# Bluepill_and_Power.net
KiCad netlist of a schematic drawn in Altium Designer
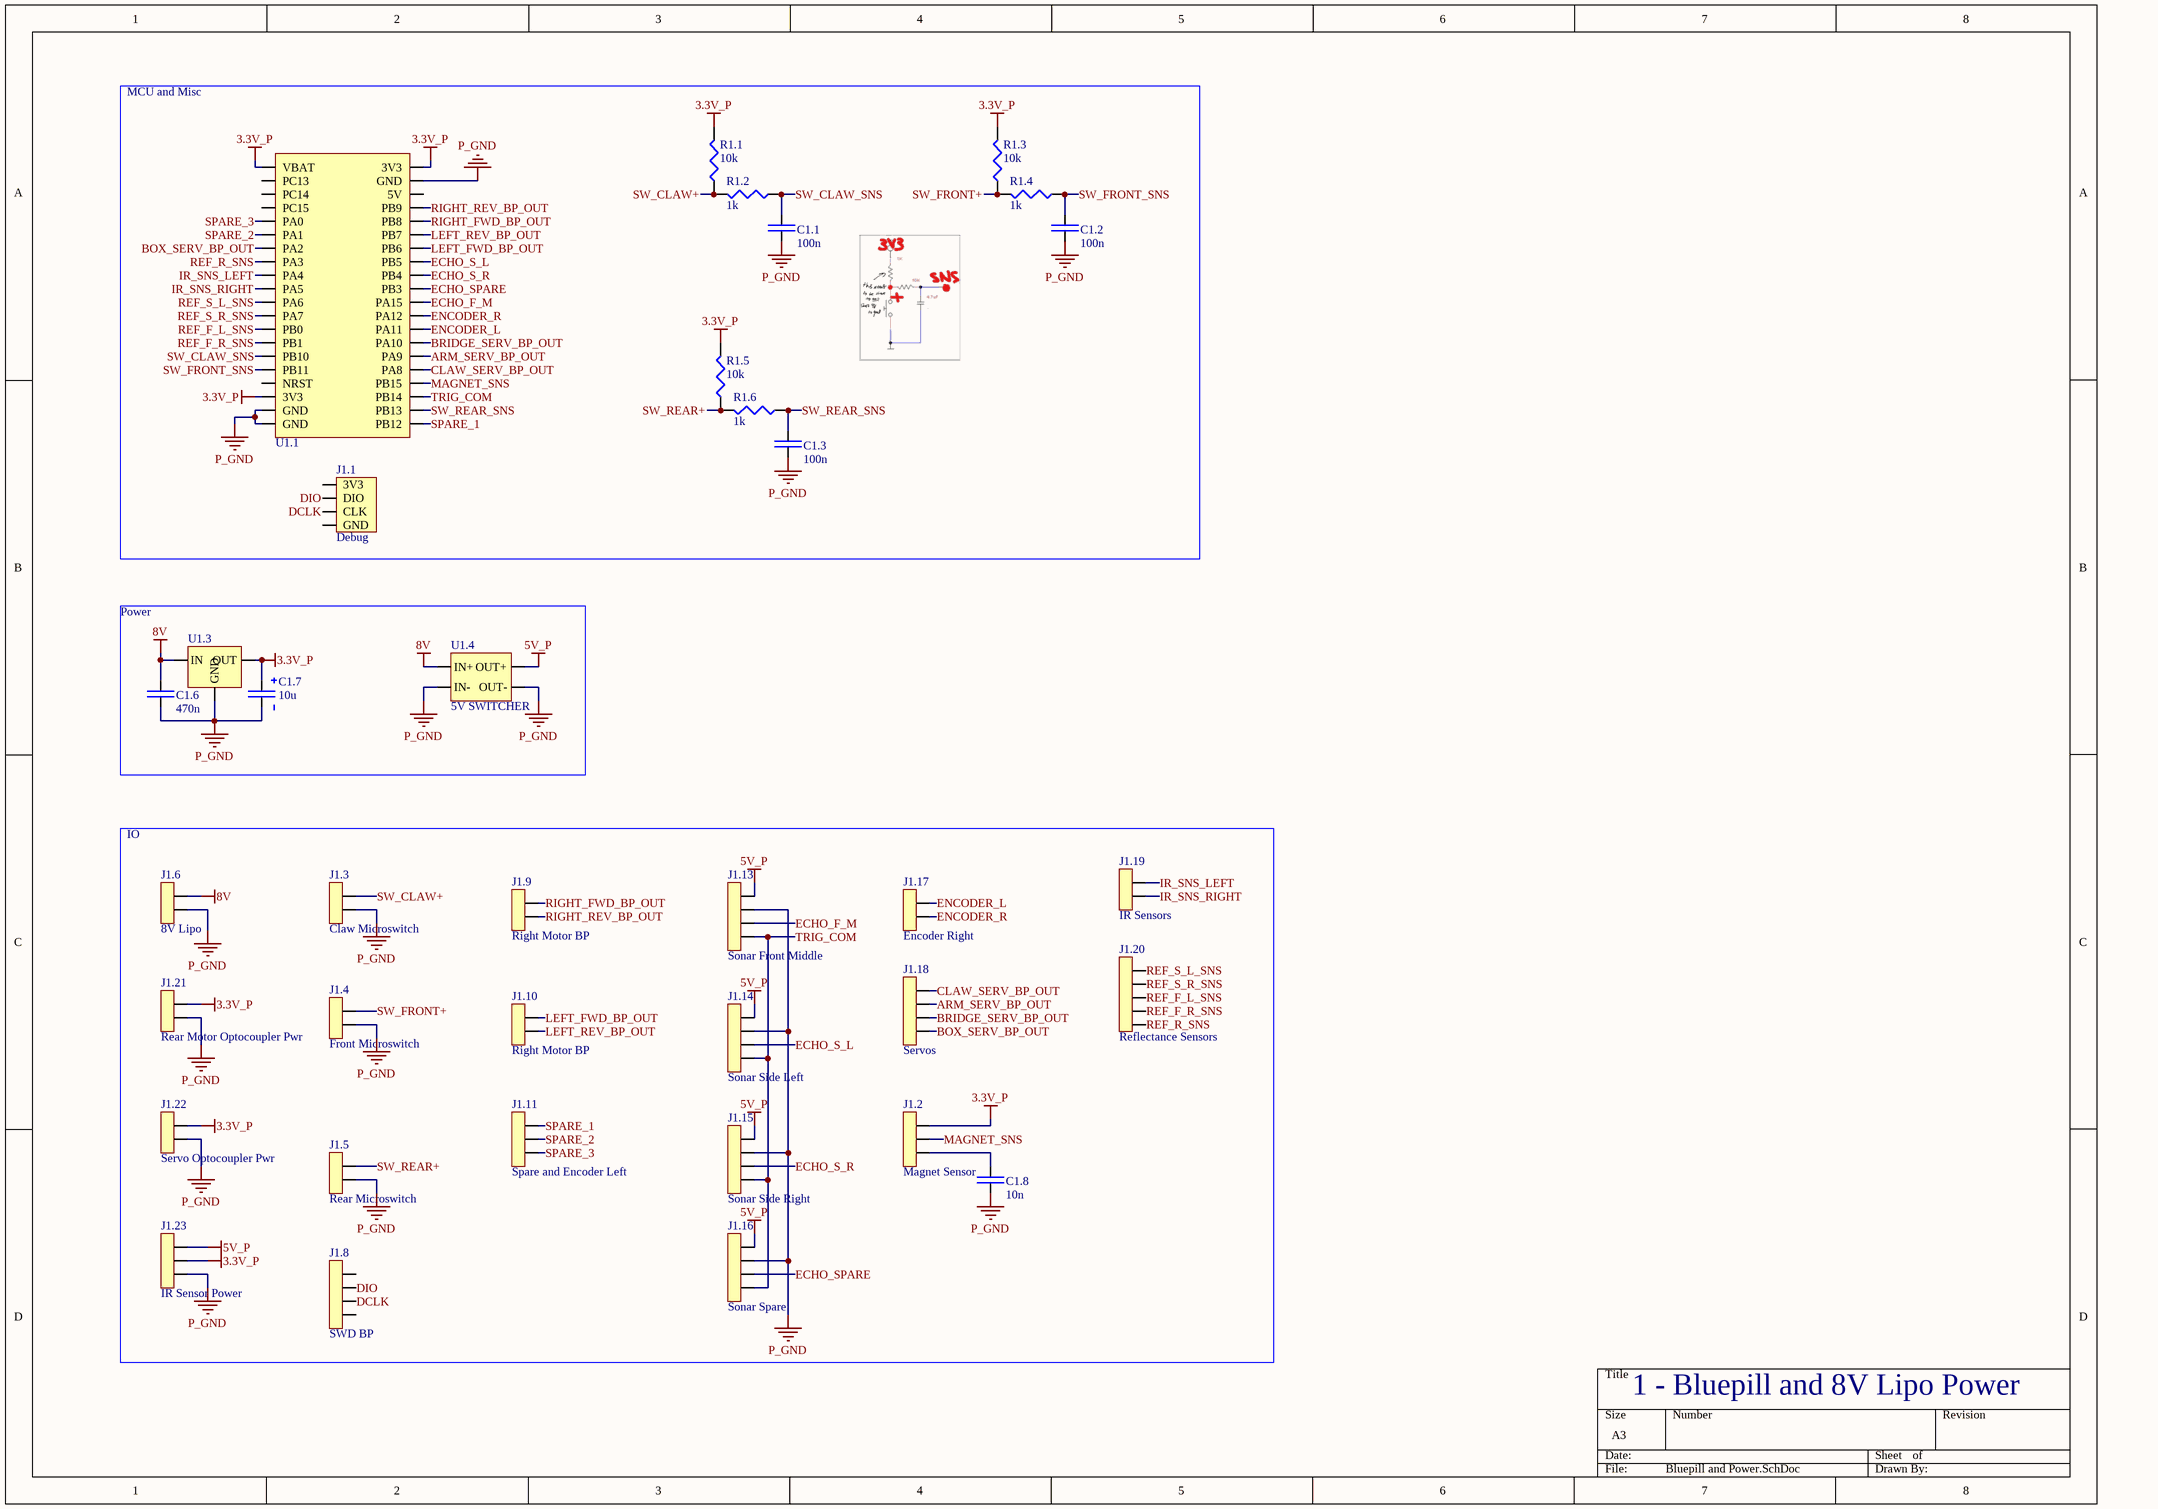
[diagram p0: Bluepill and Power.SchDoc]

(export (version "E")
  (design (tool "Eeschema 10.0.6"))
  (components
    (comp (ref "C1.1")
      (value "100n")
      (footprint "Non Polarized Cap")
      (libsource (lib "SPICEBot_SchLib") (part "Cap_Generic"))
    )
    (comp (ref "C1.2")
      (value "100n")
      (footprint "Non Polarized Cap")
      (libsource (lib "SPICEBot_SchLib") (part "Cap_Generic"))
    )
    (comp (ref "C1.3")
      (value "100n")
      (footprint "Non Polarized Cap")
      (libsource (lib "SPICEBot_SchLib") (part "Cap_Generic"))
    )
    (comp (ref "C1.6")
      (value "470n")
      (footprint "Non Polarized Cap")
      (libsource (lib "SPICEBot_SchLib") (part "Cap_Generic"))
    )
    (comp (ref "C1.7")
      (value "10u")
      (footprint "Polarized Cap")
      (libsource (lib "SPICEBot_SchLib") (part "Polarized Cap"))
    )
    (comp (ref "C1.8")
      (value "10n")
      (footprint "Non Polarized Cap")
      (libsource (lib "SPICEBot_SchLib") (part "Cap_Generic"))
    )
    (comp (ref "J1.1")
      (value "Debug")
      (footprint "Four Pads")
      (libsource (lib "SPICEBot_SchLib") (part "BP SWD Conn"))
    )
    (comp (ref "J1.2")
      (value "Magnet Sensor")
      (footprint "3pos JST")
      (description "3pos Conn")
      (libsource (lib "SPICEBot_SchLib") (part "3pos Conn"))
    )
    (comp (ref "J1.3")
      (value "Claw Microswitch")
      (footprint "2pos JST")
      (description "2pos Conn JST")
      (libsource (lib "SPICEBot_SchLib") (part "2pos Conn"))
    )
    (comp (ref "J1.4")
      (value "Front Microswitch")
      (footprint "2pos JST")
      (description "2pos Conn JST")
      (libsource (lib "SPICEBot_SchLib") (part "2pos Conn"))
    )
    (comp (ref "J1.5")
      (value "Rear Microswitch")
      (footprint "2pos JST")
      (description "2pos Conn JST")
      (libsource (lib "SPICEBot_SchLib") (part "2pos Conn"))
    )
    (comp (ref "J1.6")
      (value "8V Lipo")
      (footprint "2pos JST")
      (description "2pos Conn JST")
      (libsource (lib "SPICEBot_SchLib") (part "2pos Conn"))
    )
    (comp (ref "J1.8")
      (value "SWD BP")
      (footprint "4Pos JST")
      (description "4pos Conn")
      (libsource (lib "SPICEBot_SchLib") (part "4pos Conn"))
    )
    (comp (ref "J1.9")
      (value "Right Motor BP")
      (footprint "2pos JST")
      (description "2pos Conn JST")
      (libsource (lib "SPICEBot_SchLib") (part "2pos Conn"))
    )
    (comp (ref "J1.10")
      (value "Right Motor BP")
      (footprint "2pos JST")
      (description "2pos Conn JST")
      (libsource (lib "SPICEBot_SchLib") (part "2pos Conn"))
    )
    (comp (ref "J1.11")
      (value "Spare and Encoder Left")
      (footprint "3pos JST")
      (description "3pos Conn")
      (libsource (lib "SPICEBot_SchLib") (part "3pos Conn"))
    )
    (comp (ref "J1.13")
      (value "Sonar Front Middle")
      (footprint "4Pos JST")
      (description "4pos Conn")
      (libsource (lib "SPICEBot_SchLib") (part "4pos Conn"))
    )
    (comp (ref "J1.14")
      (value "Sonar Side Left")
      (footprint "4Pos JST")
      (description "4pos Conn")
      (libsource (lib "SPICEBot_SchLib") (part "4pos Conn"))
    )
    (comp (ref "J1.15")
      (value "Sonar Side Right")
      (footprint "4Pos JST")
      (description "4pos Conn")
      (libsource (lib "SPICEBot_SchLib") (part "4pos Conn"))
    )
    (comp (ref "J1.16")
      (value "Sonar Spare")
      (footprint "4Pos JST")
      (description "4pos Conn")
      (libsource (lib "SPICEBot_SchLib") (part "4pos Conn"))
    )
    (comp (ref "J1.17")
      (value "Encoder Right")
      (footprint "2pos JST")
      (description "2pos Conn JST")
      (libsource (lib "SPICEBot_SchLib") (part "2pos Conn"))
    )
    (comp (ref "J1.18")
      (value "Servos")
      (footprint "4Pos JST")
      (description "4pos Conn")
      (libsource (lib "SPICEBot_SchLib") (part "4pos Conn"))
    )
    (comp (ref "J1.19")
      (value "IR Sensors")
      (footprint "2pos JST")
      (description "2pos Conn JST")
      (libsource (lib "SPICEBot_SchLib") (part "2pos Conn"))
    )
    (comp (ref "J1.20")
      (value "Reflectance Sensors")
      (footprint "5POS JST")
      (description "5pos Conn JST")
      (libsource (lib "SPICEBot_SchLib") (part "5pos Conn"))
    )
    (comp (ref "J1.21")
      (value "Rear Motor Optocoupler Pwr")
      (footprint "2pos JST")
      (description "2pos Conn JST")
      (libsource (lib "SPICEBot_SchLib") (part "2pos Conn"))
    )
    (comp (ref "J1.22")
      (value "Servo Optocoupler Pwr")
      (footprint "2pos JST")
      (description "2pos Conn JST")
      (libsource (lib "SPICEBot_SchLib") (part "2pos Conn"))
    )
    (comp (ref "J1.23")
      (value "IR Sensor Power")
      (footprint "3pos JST")
      (description "3pos Conn")
      (libsource (lib "SPICEBot_SchLib") (part "3pos Conn"))
    )
    (comp (ref "R1.1")
      (value "10k")
      (footprint "Res_Generic")
      (libsource (lib "SPICEBot_SchLib") (part "Res_Generic"))
    )
    (comp (ref "R1.2")
      (value "1k")
      (footprint "Res_Generic")
      (libsource (lib "SPICEBot_SchLib") (part "Res_Generic"))
    )
    (comp (ref "R1.3")
      (value "10k")
      (footprint "Res_Generic")
      (libsource (lib "SPICEBot_SchLib") (part "Res_Generic"))
    )
    (comp (ref "R1.4")
      (value "1k")
      (footprint "Res_Generic")
      (libsource (lib "SPICEBot_SchLib") (part "Res_Generic"))
    )
    (comp (ref "R1.5")
      (value "10k")
      (footprint "Res_Generic")
      (libsource (lib "SPICEBot_SchLib") (part "Res_Generic"))
    )
    (comp (ref "R1.6")
      (value "1k")
      (footprint "Res_Generic")
      (libsource (lib "SPICEBot_SchLib") (part "Res_Generic"))
    )
    (comp (ref "U1.1")
      (value "Bluepill")
      (footprint "DIP40")
      (description "STM32F103C8T6")
      (libsource (lib "SPICEBot_SchLib") (part "Bluepill"))
    )
    (comp (ref "U1.3")
      (value "3.3V")
      (footprint "TO220")
      (description "MC33269 IC REG LINEAR 3.3V 800MA TO220-3")
      (libsource (lib "SPICEBot_SchLib") (part "MC33269 3.3V Reg"))
    )
    (comp (ref "U1.4")
      (value "5V SWITCHER")
      (footprint "ADJ Switcher")
      (description "Adjutable Switcher 3.5A Max")
      (libsource (lib "SPICEBot_SchLib") (part "LM2596S"))
    )
  )
  (nets
    (net (code "1") (name "/ARM_SERV_BP_OUT") (class "Default")
      (node (ref "J1.18") (pin "3") (pinfunction "3_3") (pintype "passive"))
      (node (ref "U1.1") (pin "26") (pinfunction "PA9_26") (pintype "passive"))
    )
    (net (code "2") (name "/BOX_SERV_BP_OUT") (class "Default")
      (node (ref "J1.18") (pin "1") (pinfunction "1_1") (pintype "passive"))
      (node (ref "U1.1") (pin "7") (pinfunction "PA2_7") (pintype "passive"))
    )
    (net (code "3") (name "/BRIDGE_SERV_BP_OUT") (class "Default")
      (node (ref "J1.18") (pin "2") (pinfunction "2_2") (pintype "passive"))
      (node (ref "U1.1") (pin "27") (pinfunction "PA10_27") (pintype "passive"))
    )
    (net (code "4") (name "/CLAW_SERV_BP_OUT") (class "Default")
      (node (ref "J1.18") (pin "4") (pinfunction "4_4") (pintype "passive"))
      (node (ref "U1.1") (pin "25") (pinfunction "PA8_25") (pintype "passive"))
    )
    (net (code "5") (name "/DCLK") (class "Default")
      (node (ref "J1.1") (pin "3") (pinfunction "CLK_3") (pintype "passive"))
      (node (ref "J1.8") (pin "2") (pinfunction "2_2") (pintype "passive"))
    )
    (net (code "6") (name "/DIO") (class "Default")
      (node (ref "J1.1") (pin "2") (pinfunction "DIO_2") (pintype "passive"))
      (node (ref "J1.8") (pin "3") (pinfunction "3_3") (pintype "passive"))
    )
    (net (code "7") (name "/ECHO_F_M") (class "Default")
      (node (ref "J1.13") (pin "2") (pinfunction "2_2") (pintype "passive"))
      (node (ref "U1.1") (pin "30") (pinfunction "PA15_30") (pintype "passive"))
    )
    (net (code "8") (name "/ECHO_SPARE") (class "Default")
      (node (ref "J1.16") (pin "2") (pinfunction "2_2") (pintype "passive"))
      (node (ref "U1.1") (pin "31") (pinfunction "PB3_31") (pintype "passive"))
    )
    (net (code "9") (name "/ECHO_S_L") (class "Default")
      (node (ref "J1.14") (pin "2") (pinfunction "2_2") (pintype "passive"))
      (node (ref "U1.1") (pin "33") (pinfunction "PB5_33") (pintype "passive"))
    )
    (net (code "10") (name "/ECHO_S_R") (class "Default")
      (node (ref "J1.15") (pin "2") (pinfunction "2_2") (pintype "passive"))
      (node (ref "U1.1") (pin "32") (pinfunction "PB4_32") (pintype "passive"))
    )
    (net (code "11") (name "/ENCODER_L") (class "Default")
      (node (ref "J1.17") (pin "2") (pinfunction "2_2") (pintype "passive"))
      (node (ref "U1.1") (pin "28") (pinfunction "PA11_28") (pintype "passive"))
    )
    (net (code "12") (name "/ENCODER_R") (class "Default")
      (node (ref "J1.17") (pin "1") (pinfunction "1_1") (pintype "passive"))
      (node (ref "U1.1") (pin "29") (pinfunction "PA12_29") (pintype "passive"))
    )
    (net (code "13") (name "/IR_SNS_LEFT") (class "Default")
      (node (ref "J1.19") (pin "2") (pinfunction "2_2") (pintype "passive"))
      (node (ref "U1.1") (pin "9") (pinfunction "PA4_9") (pintype "passive"))
    )
    (net (code "14") (name "/IR_SNS_RIGHT") (class "Default")
      (node (ref "J1.19") (pin "1") (pinfunction "1_1") (pintype "passive"))
      (node (ref "U1.1") (pin "10") (pinfunction "PA5_10") (pintype "passive"))
    )
    (net (code "15") (name "/LEFT_FWD_BP_OUT") (class "Default")
      (node (ref "J1.10") (pin "2") (pinfunction "2_2") (pintype "passive"))
      (node (ref "U1.1") (pin "34") (pinfunction "PB6_34") (pintype "passive"))
    )
    (net (code "16") (name "/LEFT_REV_BP_OUT") (class "Default")
      (node (ref "J1.10") (pin "1") (pinfunction "1_1") (pintype "passive"))
      (node (ref "U1.1") (pin "35") (pinfunction "PB7_35") (pintype "passive"))
    )
    (net (code "17") (name "/MAGNET_SNS") (class "Default")
      (node (ref "J1.2") (pin "2") (pinfunction "2_2") (pintype "passive"))
      (node (ref "U1.1") (pin "24") (pinfunction "PB15_24") (pintype "passive"))
    )
    (net (code "18") (name "/REF_F_L_SNS") (class "Default")
      (node (ref "J1.20") (pin "2") (pinfunction "2_2") (pintype "passive"))
      (node (ref "U1.1") (pin "13") (pinfunction "PB0_13") (pintype "passive"))
    )
    (net (code "19") (name "/REF_F_R_SNS") (class "Default")
      (node (ref "J1.20") (pin "1") (pinfunction "1_1") (pintype "passive"))
      (node (ref "U1.1") (pin "14") (pinfunction "PB1_14") (pintype "passive"))
    )
    (net (code "20") (name "/REF_R_SNS") (class "Default")
      (node (ref "J1.20") (pin "5") (pinfunction "5_5") (pintype "passive"))
      (node (ref "U1.1") (pin "8") (pinfunction "PA3_8") (pintype "passive"))
    )
    (net (code "21") (name "/REF_S_L_SNS") (class "Default")
      (node (ref "J1.20") (pin "4") (pinfunction "4_4") (pintype "passive"))
      (node (ref "U1.1") (pin "11") (pinfunction "PA6_11") (pintype "passive"))
    )
    (net (code "22") (name "/REF_S_R_SNS") (class "Default")
      (node (ref "J1.20") (pin "3") (pinfunction "3_3") (pintype "passive"))
      (node (ref "U1.1") (pin "12") (pinfunction "PA7_12") (pintype "passive"))
    )
    (net (code "23") (name "/RIGHT_FWD_BP_OUT") (class "Default")
      (node (ref "J1.9") (pin "2") (pinfunction "2_2") (pintype "passive"))
      (node (ref "U1.1") (pin "36") (pinfunction "PB8_36") (pintype "passive"))
    )
    (net (code "24") (name "/RIGHT_REV_BP_OUT") (class "Default")
      (node (ref "J1.9") (pin "1") (pinfunction "1_1") (pintype "passive"))
      (node (ref "U1.1") (pin "37") (pinfunction "PB9_37") (pintype "passive"))
    )
    (net (code "25") (name "/SPARE_1") (class "Default")
      (node (ref "J1.11") (pin "3") (pinfunction "3_3") (pintype "passive"))
      (node (ref "U1.1") (pin "21") (pinfunction "PB12_21") (pintype "passive"))
    )
    (net (code "26") (name "/SPARE_2") (class "Default")
      (node (ref "J1.11") (pin "2") (pinfunction "2_2") (pintype "passive"))
      (node (ref "U1.1") (pin "6") (pinfunction "PA1_6") (pintype "passive"))
    )
    (net (code "27") (name "/SPARE_3") (class "Default")
      (node (ref "J1.11") (pin "1") (pinfunction "1_1") (pintype "passive"))
      (node (ref "U1.1") (pin "5") (pinfunction "PA0_5") (pintype "passive"))
    )
    (net (code "28") (name "/SW_CLAW+") (class "Default")
      (node (ref "J1.3") (pin "2") (pinfunction "2_2") (pintype "passive"))
      (node (ref "R1.1") (pin "1") (pinfunction "1_1") (pintype "passive"))
      (node (ref "R1.2") (pin "2") (pinfunction "2_2") (pintype "passive"))
    )
    (net (code "29") (name "/SW_CLAW_SNS") (class "Default")
      (node (ref "C1.1") (pin "2") (pinfunction "2_2") (pintype "passive"))
      (node (ref "R1.2") (pin "1") (pinfunction "1_1") (pintype "passive"))
      (node (ref "U1.1") (pin "15") (pinfunction "PB10_15") (pintype "passive"))
    )
    (net (code "30") (name "/SW_FRONT+") (class "Default")
      (node (ref "J1.4") (pin "2") (pinfunction "2_2") (pintype "passive"))
      (node (ref "R1.3") (pin "1") (pinfunction "1_1") (pintype "passive"))
      (node (ref "R1.4") (pin "2") (pinfunction "2_2") (pintype "passive"))
    )
    (net (code "31") (name "/SW_FRONT_SNS") (class "Default")
      (node (ref "C1.2") (pin "2") (pinfunction "2_2") (pintype "passive"))
      (node (ref "R1.4") (pin "1") (pinfunction "1_1") (pintype "passive"))
      (node (ref "U1.1") (pin "16") (pinfunction "PB11_16") (pintype "passive"))
    )
    (net (code "32") (name "/SW_REAR+") (class "Default")
      (node (ref "J1.5") (pin "2") (pinfunction "2_2") (pintype "passive"))
      (node (ref "R1.5") (pin "1") (pinfunction "1_1") (pintype "passive"))
      (node (ref "R1.6") (pin "2") (pinfunction "2_2") (pintype "passive"))
    )
    (net (code "33") (name "/SW_REAR_SNS") (class "Default")
      (node (ref "C1.3") (pin "2") (pinfunction "2_2") (pintype "passive"))
      (node (ref "R1.6") (pin "1") (pinfunction "1_1") (pintype "passive"))
      (node (ref "U1.1") (pin "22") (pinfunction "PB13_22") (pintype "passive"))
    )
    (net (code "34") (name "/TRIG_COM") (class "Default")
      (node (ref "J1.13") (pin "1") (pinfunction "1_1") (pintype "passive"))
      (node (ref "J1.14") (pin "1") (pinfunction "1_1") (pintype "passive"))
      (node (ref "J1.15") (pin "1") (pinfunction "1_1") (pintype "passive"))
      (node (ref "J1.16") (pin "1") (pinfunction "1_1") (pintype "passive"))
      (node (ref "U1.1") (pin "23") (pinfunction "PB14_23") (pintype "passive"))
    )
    (net (code "35") (name "3.3V_P") (class "Default")
      (node (ref "C1.7") (pin "1") (pinfunction "1_1") (pintype "passive"))
      (node (ref "J1.2") (pin "3") (pinfunction "3_3") (pintype "passive"))
      (node (ref "J1.21") (pin "2") (pinfunction "2_2") (pintype "passive"))
      (node (ref "J1.22") (pin "2") (pinfunction "2_2") (pintype "passive"))
      (node (ref "J1.23") (pin "2") (pinfunction "2_2") (pintype "passive"))
      (node (ref "R1.1") (pin "2") (pinfunction "2_2") (pintype "passive"))
      (node (ref "R1.3") (pin "2") (pinfunction "2_2") (pintype "passive"))
      (node (ref "R1.5") (pin "2") (pinfunction "2_2") (pintype "passive"))
      (node (ref "U1.1") (pin "1") (pinfunction "VBAT_1") (pintype "passive"))
      (node (ref "U1.1") (pin "18") (pinfunction "3V3_18") (pintype "passive"))
      (node (ref "U1.1") (pin "40") (pinfunction "3V3_40") (pintype "passive"))
      (node (ref "U1.3") (pin "2") (pinfunction "OUT_2") (pintype "passive"))
    )
    (net (code "36") (name "5V_P") (class "Default")
      (node (ref "J1.13") (pin "4") (pinfunction "4_4") (pintype "passive"))
      (node (ref "J1.14") (pin "4") (pinfunction "4_4") (pintype "passive"))
      (node (ref "J1.15") (pin "4") (pinfunction "4_4") (pintype "passive"))
      (node (ref "J1.16") (pin "4") (pinfunction "4_4") (pintype "passive"))
      (node (ref "J1.23") (pin "3") (pinfunction "3_3") (pintype "passive"))
      (node (ref "U1.4") (pin "4") (pinfunction "OUT+_4") (pintype "passive"))
    )
    (net (code "37") (name "8V") (class "Default")
      (node (ref "C1.6") (pin "2") (pinfunction "2_2") (pintype "passive"))
      (node (ref "J1.6") (pin "2") (pinfunction "2_2") (pintype "passive"))
      (node (ref "U1.3") (pin "3") (pinfunction "IN_3") (pintype "passive"))
      (node (ref "U1.4") (pin "1") (pinfunction "IN+_1") (pintype "passive"))
    )
    (net (code "38") (name "Net-(C1.8-Pad2)") (class "Default")
      (node (ref "C1.8") (pin "2") (pinfunction "2_2") (pintype "passive"))
      (node (ref "J1.2") (pin "1") (pinfunction "1_1") (pintype "passive"))
    )
    (net (code "39") (name "P_GND") (class "Default")
      (node (ref "C1.1") (pin "1") (pinfunction "1_1") (pintype "passive"))
      (node (ref "C1.2") (pin "1") (pinfunction "1_1") (pintype "passive"))
      (node (ref "C1.3") (pin "1") (pinfunction "1_1") (pintype "passive"))
      (node (ref "C1.6") (pin "1") (pinfunction "1_1") (pintype "passive"))
      (node (ref "C1.7") (pin "2") (pinfunction "2_2") (pintype "passive"))
      (node (ref "C1.8") (pin "1") (pinfunction "1_1") (pintype "passive"))
      (node (ref "J1.13") (pin "3") (pinfunction "3_3") (pintype "passive"))
      (node (ref "J1.14") (pin "3") (pinfunction "3_3") (pintype "passive"))
      (node (ref "J1.15") (pin "3") (pinfunction "3_3") (pintype "passive"))
      (node (ref "J1.16") (pin "3") (pinfunction "3_3") (pintype "passive"))
      (node (ref "J1.21") (pin "1") (pinfunction "1_1") (pintype "passive"))
      (node (ref "J1.22") (pin "1") (pinfunction "1_1") (pintype "passive"))
      (node (ref "J1.23") (pin "1") (pinfunction "1_1") (pintype "passive"))
      (node (ref "J1.3") (pin "1") (pinfunction "1_1") (pintype "passive"))
      (node (ref "J1.4") (pin "1") (pinfunction "1_1") (pintype "passive"))
      (node (ref "J1.5") (pin "1") (pinfunction "1_1") (pintype "passive"))
      (node (ref "J1.6") (pin "1") (pinfunction "1_1") (pintype "passive"))
      (node (ref "U1.1") (pin "19") (pinfunction "GND_19") (pintype "passive"))
      (node (ref "U1.1") (pin "20") (pinfunction "GND_20") (pintype "passive"))
      (node (ref "U1.1") (pin "39") (pinfunction "GND_39") (pintype "passive"))
      (node (ref "U1.3") (pin "1") (pinfunction "GND_1") (pintype "passive"))
      (node (ref "U1.4") (pin "2") (pinfunction "IN-_2") (pintype "passive"))
      (node (ref "U1.4") (pin "3") (pinfunction "OUT-_3") (pintype "passive"))
    )
    (net (code "40") (name "unconnected-(J1.1-3V3-Pad1)") (class "Default")
      (node (ref "J1.1") (pin "1") (pinfunction "3V3_1") (pintype "passive"))
    )
    (net (code "41") (name "unconnected-(J1.1-GND-Pad4)") (class "Default")
      (node (ref "J1.1") (pin "4") (pinfunction "GND_4") (pintype "passive"))
    )
    (net (code "42") (name "unconnected-(J1.8-Pad1)") (class "Default")
      (node (ref "J1.8") (pin "1") (pinfunction "1_1") (pintype "passive"))
    )
    (net (code "43") (name "unconnected-(J1.8-Pad4)") (class "Default")
      (node (ref "J1.8") (pin "4") (pinfunction "4_4") (pintype "passive"))
    )
    (net (code "44") (name "unconnected-(U1.1-5V-Pad38)") (class "Default")
      (node (ref "U1.1") (pin "38") (pinfunction "5V_38") (pintype "passive"))
    )
    (net (code "45") (name "unconnected-(U1.1-NRST-Pad17)") (class "Default")
      (node (ref "U1.1") (pin "17") (pinfunction "NRST_17") (pintype "passive"))
    )
    (net (code "46") (name "unconnected-(U1.1-PC13-Pad2)") (class "Default")
      (node (ref "U1.1") (pin "2") (pinfunction "PC13_2") (pintype "passive"))
    )
    (net (code "47") (name "unconnected-(U1.1-PC14-Pad3)") (class "Default")
      (node (ref "U1.1") (pin "3") (pinfunction "PC14_3") (pintype "passive"))
    )
    (net (code "48") (name "unconnected-(U1.1-PC15-Pad4)") (class "Default")
      (node (ref "U1.1") (pin "4") (pinfunction "PC15_4") (pintype "passive"))
    )
  )
)
